# lin_reg_schematic-powerpcb.net
KiCad netlist of a schematic drawn in EAGLE
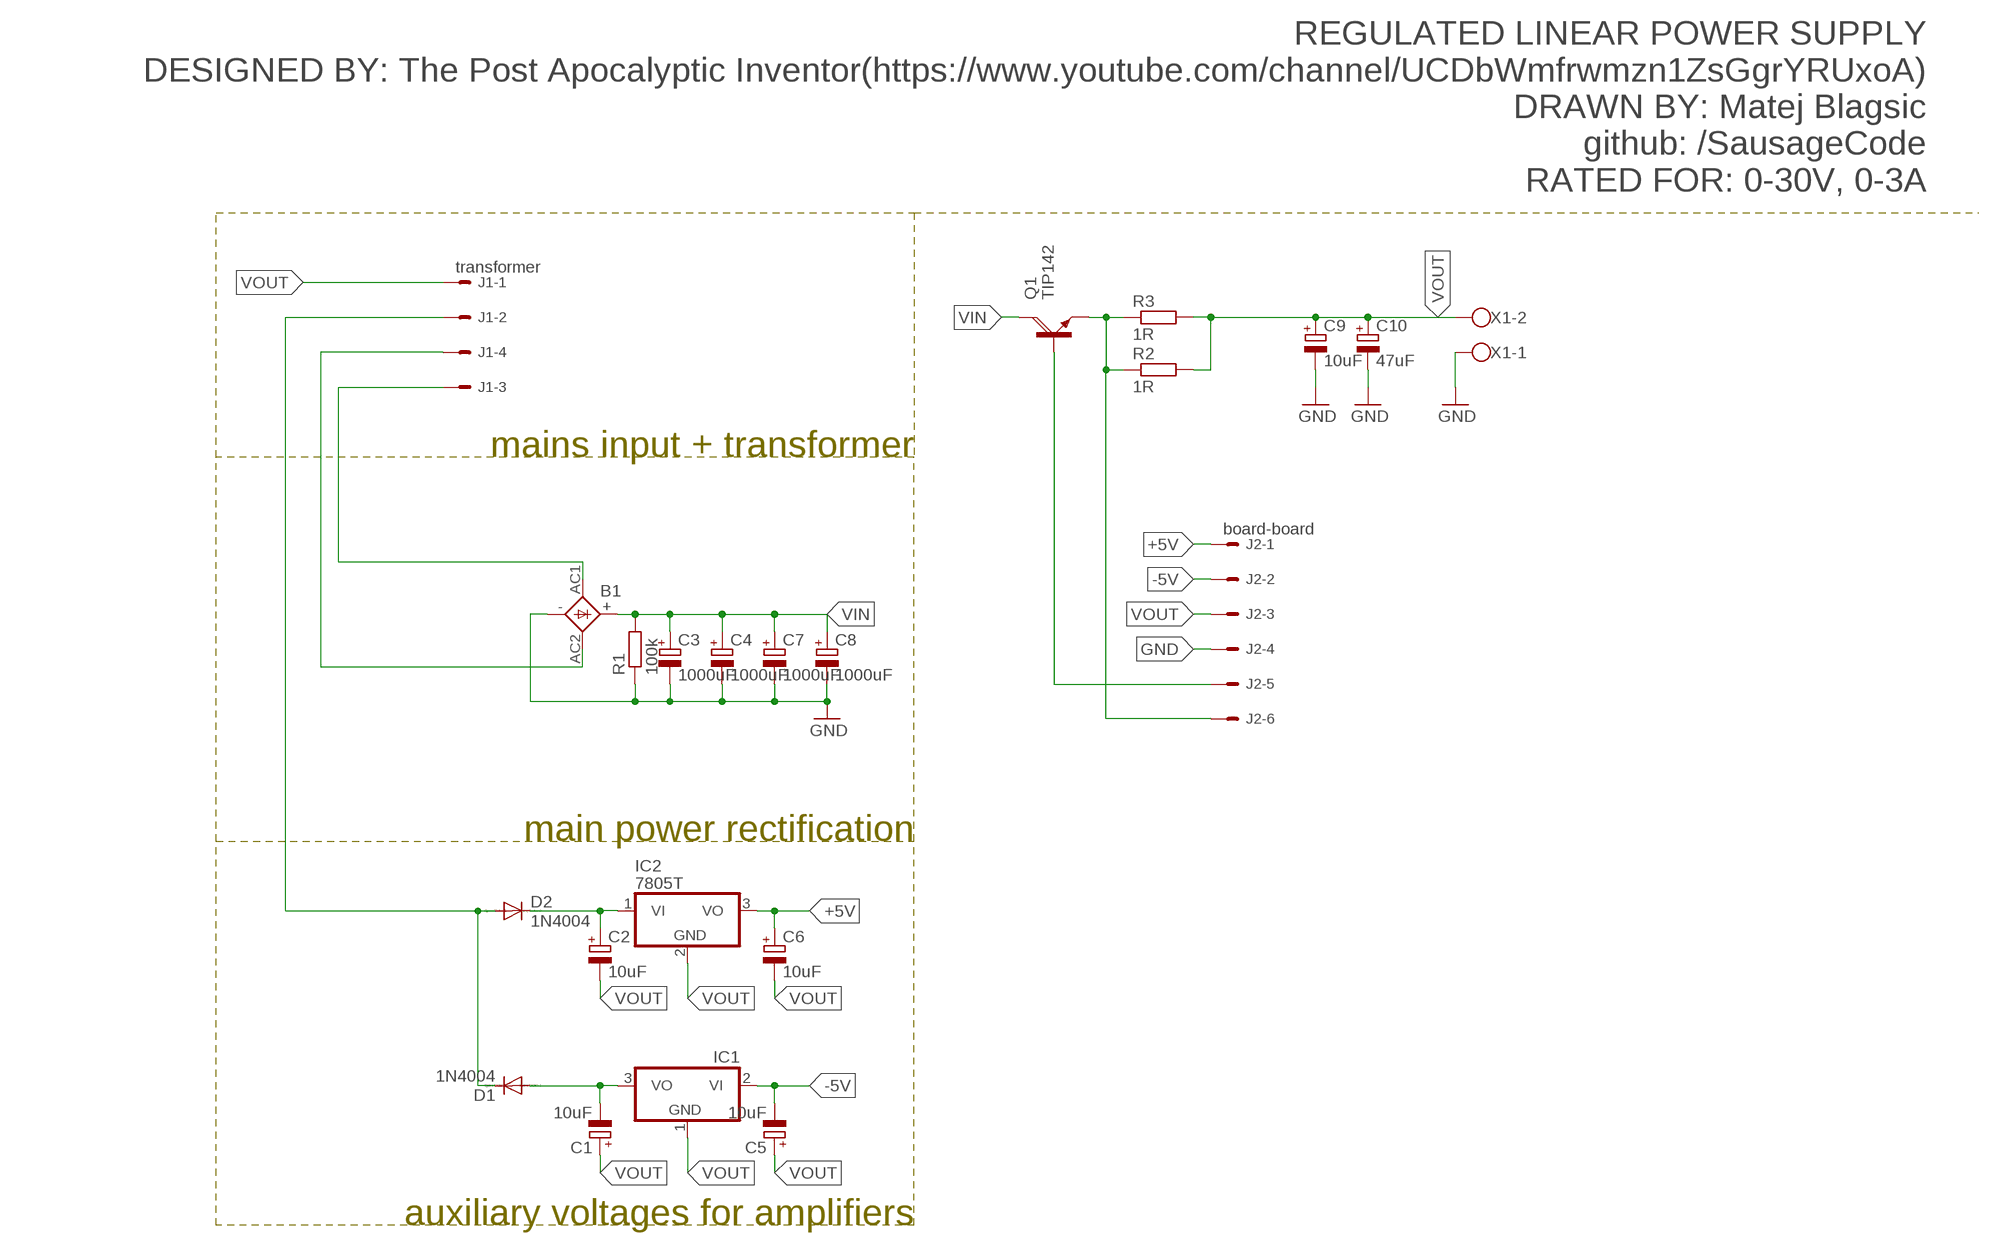
[diagram p0: schematic, sheet 1]

(export (version "E")
  (design (tool "Eeschema 10.0.6"))
  (components
    (comp (ref "B1")
      (value "2KBB-R")
      (footprint "eagle-import:2KBB-R")
      (libsource (lib "eagle-import") (part "2KBB-R"))
    )
    (comp (ref "C1")
      (value "10uF")
      (footprint "eagle-import:E2-5")
      (libsource (lib "eagle-import") (part "CPOL-EUE2-5"))
    )
    (comp (ref "C2")
      (value "10uF")
      (footprint "eagle-import:E2-5")
      (libsource (lib "eagle-import") (part "CPOL-EUE2-5"))
    )
    (comp (ref "C3")
      (value "1000uF")
      (footprint "eagle-import:E5-13")
      (libsource (lib "eagle-import") (part "CPOL-EUE5-13"))
    )
    (comp (ref "C4")
      (value "1000uF")
      (footprint "eagle-import:E5-13")
      (libsource (lib "eagle-import") (part "CPOL-EUE5-13"))
    )
    (comp (ref "C5")
      (value "10uF")
      (footprint "eagle-import:E2-5")
      (libsource (lib "eagle-import") (part "CPOL-EUE2-5"))
    )
    (comp (ref "C6")
      (value "10uF")
      (footprint "eagle-import:E2-5")
      (libsource (lib "eagle-import") (part "CPOL-EUE2-5"))
    )
    (comp (ref "C7")
      (value "1000uF")
      (footprint "eagle-import:E5-13")
      (libsource (lib "eagle-import") (part "CPOL-EUE5-13"))
    )
    (comp (ref "C8")
      (value "1000uF")
      (footprint "eagle-import:E5-13")
      (libsource (lib "eagle-import") (part "CPOL-EUE5-13"))
    )
    (comp (ref "C9")
      (value "10uF")
      (footprint "eagle-import:E2-5")
      (libsource (lib "eagle-import") (part "CPOL-EUE2-5"))
    )
    (comp (ref "C10")
      (value "47uF")
      (footprint "eagle-import:E2-5")
      (libsource (lib "eagle-import") (part "CPOL-EUE2-5"))
    )
    (comp (ref "D1")
      (value "1N4004")
      (footprint "eagle-import:DO41-10")
      (libsource (lib "eagle-import") (part "1N4004"))
    )
    (comp (ref "D2")
      (value "1N4004")
      (footprint "eagle-import:DO41-10")
      (libsource (lib "eagle-import") (part "1N4004"))
    )
    (comp (ref "IC1")
      (value "7905T")
      (footprint "eagle-import:TO220H")
      (libsource (lib "eagle-import") (part "79T05"))
    )
    (comp (ref "IC2")
      (value "7805T")
      (footprint "eagle-import:TO220H")
      (libsource (lib "eagle-import") (part "78T05"))
    )
    (comp (ref "J1")
      (value "transformer")
      (footprint "eagle-import:6410-04")
      (libsource (lib "eagle-import") (part "22-?-0427-2041"))
    )
    (comp (ref "J2")
      (value "board-board")
      (footprint "eagle-import:6410-06")
      (libsource (lib "eagle-import") (part "22-?-0627-2061"))
    )
    (comp (ref "Q1")
      (value "TIP142")
      (footprint "eagle-import:SOT93")
      (libsource (lib "eagle-import") (part "TIP142"))
    )
    (comp (ref "R1")
      (value "100k")
      (footprint "eagle-import:0309_12")
      (libsource (lib "eagle-import") (part "R-EU_0309/12"))
    )
    (comp (ref "R2")
      (value "1R")
      (footprint "eagle-import:0922_22")
      (libsource (lib "eagle-import") (part "resistor_348_R-EU_0922/22"))
    )
    (comp (ref "R3")
      (value "1R")
      (footprint "eagle-import:0922_22")
      (libsource (lib "eagle-import") (part "resistor_348_R-EU_0922/22"))
    )
    (comp (ref "X1")
      (value "W237-102")
      (footprint "eagle-import:W237-102")
      (fields (field (name "MPN") "237-102"))
      (libsource (lib "eagle-import") (part "W237-102"))
    )
  )
  (nets
    (net (code "1") (name "+5V") (class "Default")
      (node (ref "C6") (pin "+") (pinfunction "+_+") (pintype "passive"))
      (node (ref "IC2") (pin "3") (pinfunction "VO_3") (pintype "passive"))
      (node (ref "J2") (pin "1") (pinfunction "S_1") (pintype "passive"))
    )
    (net (code "2") (name "-5V") (class "Default")
      (node (ref "C5") (pin "-") (pinfunction "-_-") (pintype "passive"))
      (node (ref "IC1") (pin "2") (pinfunction "VI_2") (pintype "input"))
      (node (ref "J2") (pin "2") (pinfunction "S_2") (pintype "passive"))
    )
    (net (code "3") (name "GND") (class "Default")
      (node (ref "B1") (pin "-") (pinfunction "-_-") (pintype "passive"))
      (node (ref "C10") (pin "-") (pinfunction "-_-") (pintype "passive"))
      (node (ref "C3") (pin "-") (pinfunction "-_-") (pintype "passive"))
      (node (ref "C4") (pin "-") (pinfunction "-_-") (pintype "passive"))
      (node (ref "C7") (pin "-") (pinfunction "-_-") (pintype "passive"))
      (node (ref "C8") (pin "-") (pinfunction "-_-") (pintype "passive"))
      (node (ref "C9") (pin "-") (pinfunction "-_-") (pintype "passive"))
      (node (ref "J2") (pin "4") (pinfunction "S_4") (pintype "passive"))
      (node (ref "R1") (pin "1") (pinfunction "1_1") (pintype "passive"))
      (node (ref "X1") (pin "1") (pinfunction "KL_1") (pintype "passive"))
    )
    (net (code "4") (name "Net-(IC1-VO)") (class "Default")
      (node (ref "C1") (pin "-") (pinfunction "-_-") (pintype "passive"))
      (node (ref "D1") (pin "A") (pinfunction "A_A") (pintype "passive"))
      (node (ref "IC1") (pin "3") (pinfunction "VO_3") (pintype "passive"))
    )
    (net (code "5") (name "Net-(IC2-VI)") (class "Default")
      (node (ref "C2") (pin "+") (pinfunction "+_+") (pintype "passive"))
      (node (ref "D2") (pin "C") (pinfunction "C_C") (pintype "passive"))
      (node (ref "IC2") (pin "1") (pinfunction "VI_1") (pintype "input"))
    )
    (net (code "6") (name "Net-(J1B-S)") (class "Default")
      (node (ref "D1") (pin "C") (pinfunction "C_C") (pintype "passive"))
      (node (ref "D2") (pin "A") (pinfunction "A_A") (pintype "passive"))
      (node (ref "J1") (pin "2") (pinfunction "S_2") (pintype "passive"))
    )
    (net (code "7") (name "Net-(J1C-S)") (class "Default")
      (node (ref "B1") (pin "AC1") (pinfunction "AC1_AC1") (pintype "passive"))
      (node (ref "J1") (pin "3") (pinfunction "S_3") (pintype "passive"))
    )
    (net (code "8") (name "Net-(J1D-S)") (class "Default")
      (node (ref "B1") (pin "AC2") (pinfunction "AC2_AC2") (pintype "passive"))
      (node (ref "J1") (pin "4") (pinfunction "S_4") (pintype "passive"))
    )
    (net (code "9") (name "Net-(J2E-S)") (class "Default")
      (node (ref "J2") (pin "5") (pinfunction "S_5") (pintype "passive"))
      (node (ref "Q1") (pin "B") (pinfunction "B_B") (pintype "passive"))
    )
    (net (code "10") (name "Net-(J2F-S)") (class "Default")
      (node (ref "J2") (pin "6") (pinfunction "S_6") (pintype "passive"))
      (node (ref "Q1") (pin "E") (pinfunction "E_E") (pintype "passive"))
      (node (ref "R2") (pin "1") (pinfunction "1_1") (pintype "passive"))
      (node (ref "R3") (pin "1") (pinfunction "1_1") (pintype "passive"))
    )
    (net (code "11") (name "VIN") (class "Default")
      (node (ref "B1") (pin "+") (pinfunction "+_+") (pintype "passive"))
      (node (ref "C3") (pin "+") (pinfunction "+_+") (pintype "passive"))
      (node (ref "C4") (pin "+") (pinfunction "+_+") (pintype "passive"))
      (node (ref "C7") (pin "+") (pinfunction "+_+") (pintype "passive"))
      (node (ref "C8") (pin "+") (pinfunction "+_+") (pintype "passive"))
      (node (ref "Q1") (pin "C") (pinfunction "C_C") (pintype "passive"))
      (node (ref "R1") (pin "2") (pinfunction "2_2") (pintype "passive"))
    )
    (net (code "12") (name "VOUT") (class "Default")
      (node (ref "C1") (pin "+") (pinfunction "+_+") (pintype "passive"))
      (node (ref "C10") (pin "+") (pinfunction "+_+") (pintype "passive"))
      (node (ref "C2") (pin "-") (pinfunction "-_-") (pintype "passive"))
      (node (ref "C5") (pin "+") (pinfunction "+_+") (pintype "passive"))
      (node (ref "C6") (pin "-") (pinfunction "-_-") (pintype "passive"))
      (node (ref "C9") (pin "+") (pinfunction "+_+") (pintype "passive"))
      (node (ref "IC1") (pin "1") (pinfunction "GND_1") (pintype "passive"))
      (node (ref "IC2") (pin "2") (pinfunction "GND_2") (pintype "passive"))
      (node (ref "J1") (pin "1") (pinfunction "S_1") (pintype "passive"))
      (node (ref "J2") (pin "3") (pinfunction "S_3") (pintype "passive"))
      (node (ref "R2") (pin "2") (pinfunction "2_2") (pintype "passive"))
      (node (ref "R3") (pin "2") (pinfunction "2_2") (pintype "passive"))
      (node (ref "X1") (pin "2") (pinfunction "KL_2") (pintype "passive"))
    )
  )
)
